# SCH_homework1_2025-05-07.net
KiCad netlist of a schematic drawn in EasyEDA
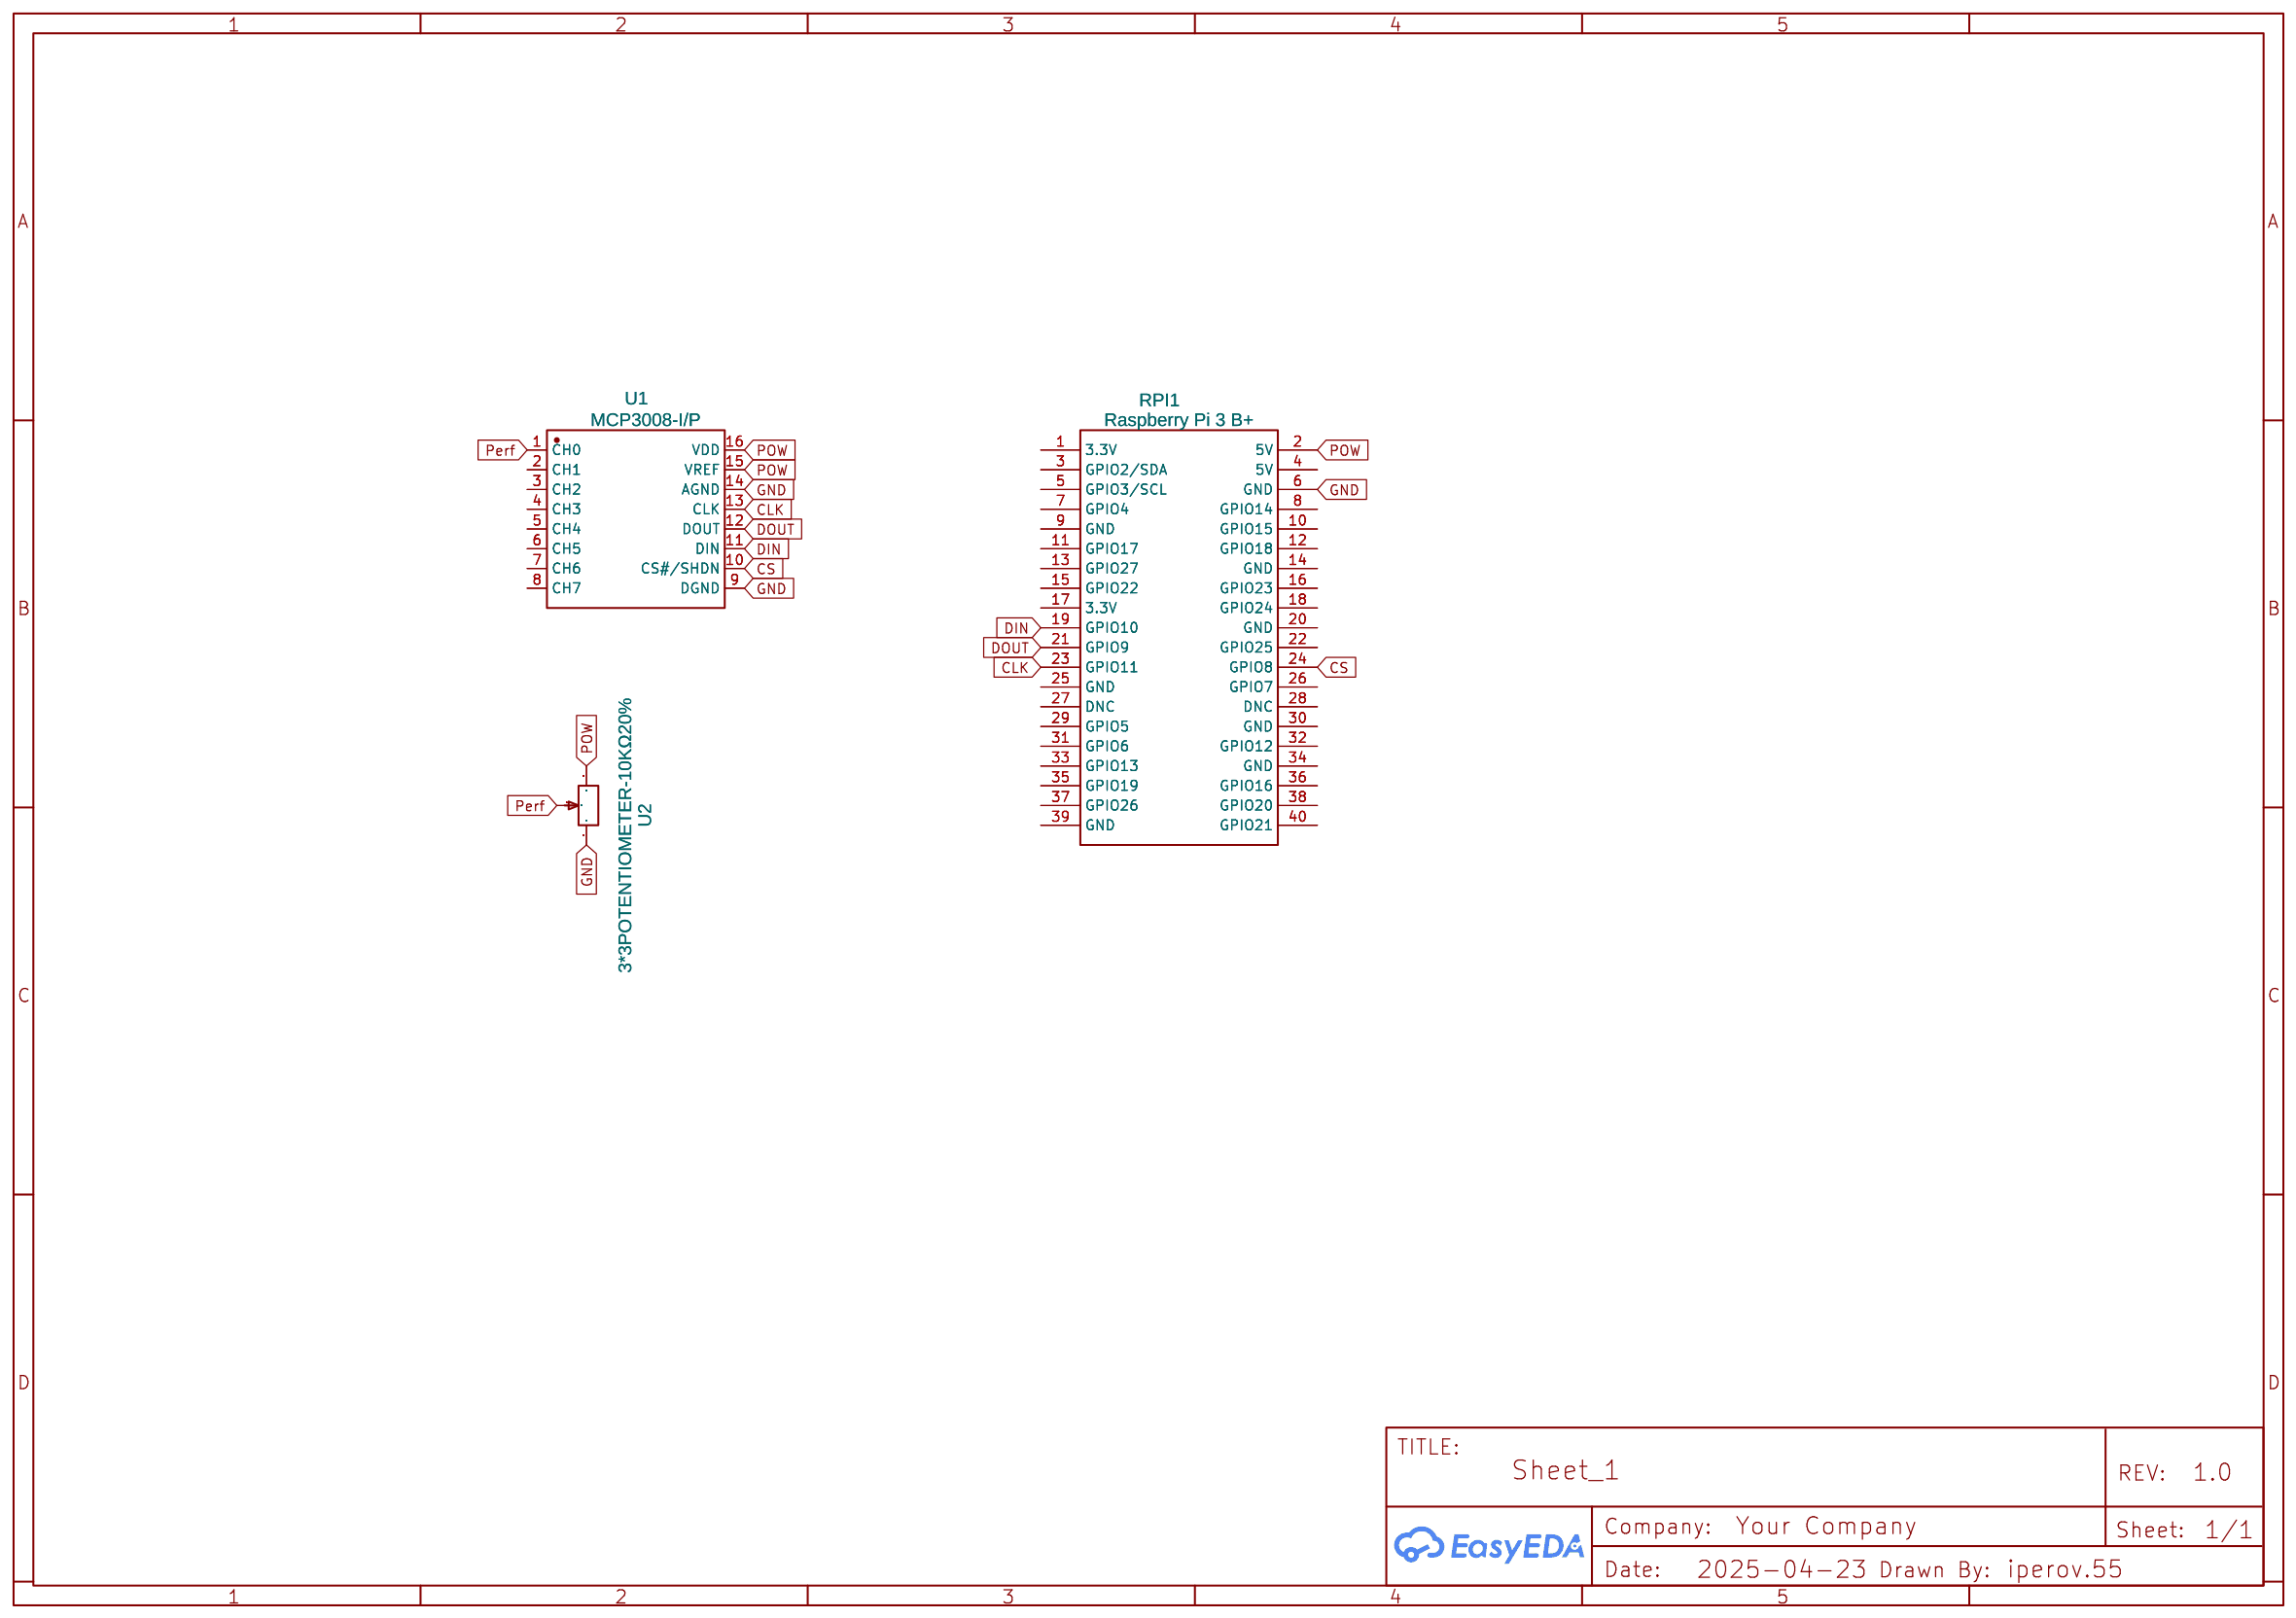
[diagram p0: schematic sheet]

(export (version "E")
  (design (tool "Eeschema 10.0.6"))
  (components
    (comp (ref "RPI1")
      (value "Raspberry Pi 3 B+")
      (fields
        (field (name "Manufacturer Part") "Raspberry Pi 3 - Model B+ - 1.4GHz Cortex-A53 with 1GB RAM")
        (field (name "Manufacturer") "Raspberry Pi")
      )
      (libsource (lib "") (part "Raspberry Pi 3 B+"))
    )
    (comp (ref "U1")
      (value "MCP3008-I/P")
      (fields (field (name "Manufacturer") "MICROCHIP(美国微芯)"))
      (libsource (lib "") (part "MCP3008-I/P"))
    )
    (comp (ref "U2")
      (value "3*3POTENTIOMETER-10KΩ20%")
      (fields (field (name "Manufacturer Part") "3*3Potentiometer-10kΩ20%"))
      (libsource (lib "") (part "3*3POTENTIOMETER-10KΩ20%"))
    )
  )
  (nets
    (net (code "1") (name "CLK") (class "Default")
      (node (ref "RPI1") (pin "23") (pinfunction "GPIO11_23") (pintype "bidirectional"))
      (node (ref "U1") (pin "13") (pinfunction "CLK_13") (pintype "unspecified"))
    )
    (net (code "2") (name "CS") (class "Default")
      (node (ref "RPI1") (pin "24") (pinfunction "GPIO8_24") (pintype "bidirectional"))
      (node (ref "U1") (pin "10") (pinfunction "CS#/SHDN_10") (pintype "unspecified"))
    )
    (net (code "3") (name "DIN") (class "Default")
      (node (ref "RPI1") (pin "19") (pinfunction "GPIO10_19") (pintype "bidirectional"))
      (node (ref "U1") (pin "11") (pinfunction "DIN_11") (pintype "unspecified"))
    )
    (net (code "4") (name "DOUT") (class "Default")
      (node (ref "RPI1") (pin "21") (pinfunction "GPIO9_21") (pintype "bidirectional"))
      (node (ref "U1") (pin "12") (pinfunction "DOUT_12") (pintype "unspecified"))
    )
    (net (code "5") (name "GND") (class "Default")
      (node (ref "RPI1") (pin "6") (pinfunction "GND_6") (pintype "unspecified"))
      (node (ref "U1") (pin "14") (pinfunction "AGND_14") (pintype "unspecified"))
      (node (ref "U1") (pin "9") (pinfunction "DGND_9") (pintype "unspecified"))
      (node (ref "U2") (pin "1") (pinfunction "1_1") (pintype "input"))
    )
    (net (code "6") (name "POW") (class "Default")
      (node (ref "RPI1") (pin "2") (pinfunction "5V_2") (pintype "passive"))
      (node (ref "U1") (pin "15") (pinfunction "VREF_15") (pintype "unspecified"))
      (node (ref "U1") (pin "16") (pinfunction "VDD_16") (pintype "unspecified"))
      (node (ref "U2") (pin "3") (pinfunction "3_3") (pintype "input"))
    )
    (net (code "7") (name "Perf") (class "Default")
      (node (ref "U1") (pin "1") (pinfunction "CH0_1") (pintype "unspecified"))
      (node (ref "U2") (pin "2") (pinfunction "2_2") (pintype "input"))
    )
    (net (code "8") (name "unconnected-(RPI1-3.3V-Pad1)") (class "Default")
      (node (ref "RPI1") (pin "1") (pinfunction "3.3V_1") (pintype "passive"))
    )
    (net (code "9") (name "unconnected-(RPI1-3.3V-Pad17)") (class "Default")
      (node (ref "RPI1") (pin "17") (pinfunction "3.3V_17") (pintype "passive"))
    )
    (net (code "10") (name "unconnected-(RPI1-5V-Pad4)") (class "Default")
      (node (ref "RPI1") (pin "4") (pinfunction "5V_4") (pintype "passive"))
    )
    (net (code "11") (name "unconnected-(RPI1-DNC-Pad27)") (class "Default")
      (node (ref "RPI1") (pin "27") (pinfunction "DNC_27") (pintype "unspecified"))
    )
    (net (code "12") (name "unconnected-(RPI1-DNC-Pad28)") (class "Default")
      (node (ref "RPI1") (pin "28") (pinfunction "DNC_28") (pintype "unspecified"))
    )
    (net (code "13") (name "unconnected-(RPI1-GND-Pad9)") (class "Default")
      (node (ref "RPI1") (pin "9") (pinfunction "GND_9") (pintype "unspecified"))
    )
    (net (code "14") (name "unconnected-(RPI1-GND-Pad14)") (class "Default")
      (node (ref "RPI1") (pin "14") (pinfunction "GND_14") (pintype "unspecified"))
    )
    (net (code "15") (name "unconnected-(RPI1-GND-Pad20)") (class "Default")
      (node (ref "RPI1") (pin "20") (pinfunction "GND_20") (pintype "unspecified"))
    )
    (net (code "16") (name "unconnected-(RPI1-GND-Pad25)") (class "Default")
      (node (ref "RPI1") (pin "25") (pinfunction "GND_25") (pintype "unspecified"))
    )
    (net (code "17") (name "unconnected-(RPI1-GND-Pad30)") (class "Default")
      (node (ref "RPI1") (pin "30") (pinfunction "GND_30") (pintype "unspecified"))
    )
    (net (code "18") (name "unconnected-(RPI1-GND-Pad34)") (class "Default")
      (node (ref "RPI1") (pin "34") (pinfunction "GND_34") (pintype "unspecified"))
    )
    (net (code "19") (name "unconnected-(RPI1-GND-Pad39)") (class "Default")
      (node (ref "RPI1") (pin "39") (pinfunction "GND_39") (pintype "unspecified"))
    )
    (net (code "20") (name "unconnected-(RPI1-GPIO2{slash}SDA-Pad3)") (class "Default")
      (node (ref "RPI1") (pin "3") (pinfunction "GPIO2/SDA_3") (pintype "bidirectional"))
    )
    (net (code "21") (name "unconnected-(RPI1-GPIO3{slash}SCL-Pad5)") (class "Default")
      (node (ref "RPI1") (pin "5") (pinfunction "GPIO3/SCL_5") (pintype "bidirectional"))
    )
    (net (code "22") (name "unconnected-(RPI1-GPIO4-Pad7)") (class "Default")
      (node (ref "RPI1") (pin "7") (pinfunction "GPIO4_7") (pintype "bidirectional"))
    )
    (net (code "23") (name "unconnected-(RPI1-GPIO5-Pad29)") (class "Default")
      (node (ref "RPI1") (pin "29") (pinfunction "GPIO5_29") (pintype "bidirectional"))
    )
    (net (code "24") (name "unconnected-(RPI1-GPIO6-Pad31)") (class "Default")
      (node (ref "RPI1") (pin "31") (pinfunction "GPIO6_31") (pintype "bidirectional"))
    )
    (net (code "25") (name "unconnected-(RPI1-GPIO7-Pad26)") (class "Default")
      (node (ref "RPI1") (pin "26") (pinfunction "GPIO7_26") (pintype "bidirectional"))
    )
    (net (code "26") (name "unconnected-(RPI1-GPIO12-Pad32)") (class "Default")
      (node (ref "RPI1") (pin "32") (pinfunction "GPIO12_32") (pintype "bidirectional"))
    )
    (net (code "27") (name "unconnected-(RPI1-GPIO13-Pad33)") (class "Default")
      (node (ref "RPI1") (pin "33") (pinfunction "GPIO13_33") (pintype "bidirectional"))
    )
    (net (code "28") (name "unconnected-(RPI1-GPIO14-Pad8)") (class "Default")
      (node (ref "RPI1") (pin "8") (pinfunction "GPIO14_8") (pintype "bidirectional"))
    )
    (net (code "29") (name "unconnected-(RPI1-GPIO15-Pad10)") (class "Default")
      (node (ref "RPI1") (pin "10") (pinfunction "GPIO15_10") (pintype "bidirectional"))
    )
    (net (code "30") (name "unconnected-(RPI1-GPIO16-Pad36)") (class "Default")
      (node (ref "RPI1") (pin "36") (pinfunction "GPIO16_36") (pintype "bidirectional"))
    )
    (net (code "31") (name "unconnected-(RPI1-GPIO17-Pad11)") (class "Default")
      (node (ref "RPI1") (pin "11") (pinfunction "GPIO17_11") (pintype "bidirectional"))
    )
    (net (code "32") (name "unconnected-(RPI1-GPIO18-Pad12)") (class "Default")
      (node (ref "RPI1") (pin "12") (pinfunction "GPIO18_12") (pintype "bidirectional"))
    )
    (net (code "33") (name "unconnected-(RPI1-GPIO19-Pad35)") (class "Default")
      (node (ref "RPI1") (pin "35") (pinfunction "GPIO19_35") (pintype "bidirectional"))
    )
    (net (code "34") (name "unconnected-(RPI1-GPIO20-Pad38)") (class "Default")
      (node (ref "RPI1") (pin "38") (pinfunction "GPIO20_38") (pintype "bidirectional"))
    )
    (net (code "35") (name "unconnected-(RPI1-GPIO21-Pad40)") (class "Default")
      (node (ref "RPI1") (pin "40") (pinfunction "GPIO21_40") (pintype "bidirectional"))
    )
    (net (code "36") (name "unconnected-(RPI1-GPIO22-Pad15)") (class "Default")
      (node (ref "RPI1") (pin "15") (pinfunction "GPIO22_15") (pintype "bidirectional"))
    )
    (net (code "37") (name "unconnected-(RPI1-GPIO23-Pad16)") (class "Default")
      (node (ref "RPI1") (pin "16") (pinfunction "GPIO23_16") (pintype "bidirectional"))
    )
    (net (code "38") (name "unconnected-(RPI1-GPIO24-Pad18)") (class "Default")
      (node (ref "RPI1") (pin "18") (pinfunction "GPIO24_18") (pintype "bidirectional"))
    )
    (net (code "39") (name "unconnected-(RPI1-GPIO25-Pad22)") (class "Default")
      (node (ref "RPI1") (pin "22") (pinfunction "GPIO25_22") (pintype "bidirectional"))
    )
    (net (code "40") (name "unconnected-(RPI1-GPIO26-Pad37)") (class "Default")
      (node (ref "RPI1") (pin "37") (pinfunction "GPIO26_37") (pintype "bidirectional"))
    )
    (net (code "41") (name "unconnected-(RPI1-GPIO27-Pad13)") (class "Default")
      (node (ref "RPI1") (pin "13") (pinfunction "GPIO27_13") (pintype "bidirectional"))
    )
    (net (code "42") (name "unconnected-(U1-CH1-Pad2)") (class "Default")
      (node (ref "U1") (pin "2") (pinfunction "CH1_2") (pintype "unspecified"))
    )
    (net (code "43") (name "unconnected-(U1-CH2-Pad3)") (class "Default")
      (node (ref "U1") (pin "3") (pinfunction "CH2_3") (pintype "unspecified"))
    )
    (net (code "44") (name "unconnected-(U1-CH3-Pad4)") (class "Default")
      (node (ref "U1") (pin "4") (pinfunction "CH3_4") (pintype "unspecified"))
    )
    (net (code "45") (name "unconnected-(U1-CH4-Pad5)") (class "Default")
      (node (ref "U1") (pin "5") (pinfunction "CH4_5") (pintype "unspecified"))
    )
    (net (code "46") (name "unconnected-(U1-CH5-Pad6)") (class "Default")
      (node (ref "U1") (pin "6") (pinfunction "CH5_6") (pintype "unspecified"))
    )
    (net (code "47") (name "unconnected-(U1-CH6-Pad7)") (class "Default")
      (node (ref "U1") (pin "7") (pinfunction "CH6_7") (pintype "unspecified"))
    )
    (net (code "48") (name "unconnected-(U1-CH7-Pad8)") (class "Default")
      (node (ref "U1") (pin "8") (pinfunction "CH7_8") (pintype "unspecified"))
    )
  )
)
